# TechnoPoliceBadge.net
KiCad netlist of a schematic drawn in Altium Designer
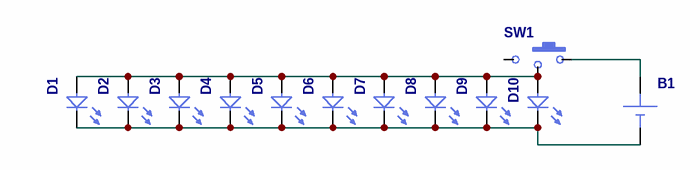
[diagram p0: TechnoPoliceBadge.SchDoc]

(export (version "E")
  (design (tool "Eeschema 10.0.6"))
  (components
    (comp (ref "B1")
      (value "BAT-HLD-001-TR")
      (footprint "BAT-HLD-001")
      (description "Coin Cell Battery Holders Linx CR2032 Battery Holder, Tape n Reel")
      (fields (field (name "MANUFACTURER") "Linx Technologies"))
      (libsource (lib "7Sigma") (part "BATT"))
    )
    (comp (ref "D1")
      (value "OL_RGB_IC_0807")
      (footprint "OL_0807")
      (description "RGB Diode with integrated driver. Fast Flashing")
      (fields (field (name "MANUFACTURER") "Aliexpress") (field (name "MANUFACTURER PART NUMBER") "None"))
      (libsource (lib "7Sigma") (part "OL_W"))
    )
    (comp (ref "D2")
      (value "OL_RGB_IC_0807")
      (footprint "OL_0807")
      (description "RGB Diode with integrated driver. Fast Flashing")
      (fields (field (name "MANUFACTURER") "Aliexpress") (field (name "MANUFACTURER PART NUMBER") "None"))
      (libsource (lib "7Sigma") (part "OL_W"))
    )
    (comp (ref "D3")
      (value "OL_RGB_IC_0807")
      (footprint "OL_0807")
      (description "RGB Diode with integrated driver. Fast Flashing")
      (fields (field (name "MANUFACTURER") "Aliexpress") (field (name "MANUFACTURER PART NUMBER") "None"))
      (libsource (lib "7Sigma") (part "OL_W"))
    )
    (comp (ref "D4")
      (value "OL_RGB_IC_0807")
      (footprint "OL_0807")
      (description "RGB Diode with integrated driver. Fast Flashing")
      (fields (field (name "MANUFACTURER") "Aliexpress") (field (name "MANUFACTURER PART NUMBER") "None"))
      (libsource (lib "7Sigma") (part "OL_W"))
    )
    (comp (ref "D5")
      (value "OL_RGB_IC_0807")
      (footprint "OL_0807")
      (description "RGB Diode with integrated driver. Fast Flashing")
      (fields (field (name "MANUFACTURER") "Aliexpress") (field (name "MANUFACTURER PART NUMBER") "None"))
      (libsource (lib "7Sigma") (part "OL_W"))
    )
    (comp (ref "D6")
      (value "OL_RGB_IC_0807")
      (footprint "OL_0807")
      (description "RGB Diode with integrated driver. Fast Flashing")
      (fields (field (name "MANUFACTURER") "Aliexpress") (field (name "MANUFACTURER PART NUMBER") "None"))
      (libsource (lib "7Sigma") (part "OL_W"))
    )
    (comp (ref "D7")
      (value "OL_RGB_IC_0807")
      (footprint "OL_0807")
      (description "RGB Diode with integrated driver. Fast Flashing")
      (fields (field (name "MANUFACTURER") "Aliexpress") (field (name "MANUFACTURER PART NUMBER") "None"))
      (libsource (lib "7Sigma") (part "OL_W"))
    )
    (comp (ref "D8")
      (value "OL_RGB_IC_0807")
      (footprint "OL_0807")
      (description "RGB Diode with integrated driver. Fast Flashing")
      (fields (field (name "MANUFACTURER") "Aliexpress") (field (name "MANUFACTURER PART NUMBER") "None"))
      (libsource (lib "7Sigma") (part "OL_W"))
    )
    (comp (ref "D9")
      (value "OL_RGB_IC_0807")
      (footprint "OL_0807")
      (description "RGB Diode with integrated driver. Fast Flashing")
      (fields (field (name "MANUFACTURER") "Aliexpress") (field (name "MANUFACTURER PART NUMBER") "None"))
      (libsource (lib "7Sigma") (part "OL_W"))
    )
    (comp (ref "D10")
      (value "OL_RGB_IC_0807")
      (footprint "OL_0807")
      (description "RGB Diode with integrated driver. Fast Flashing")
      (fields (field (name "MANUFACTURER") "Aliexpress") (field (name "MANUFACTURER PART NUMBER") "None"))
      (libsource (lib "7Sigma") (part "OL_W"))
    )
    (comp (ref "SW1")
      (value "MSK-12C01-07")
      (footprint "MSK-12C01-07")
      (description "SMT Slide Switch")
      (libsource (lib "7Sigma") (part "MSK-12C01-07"))
    )
  )
  (nets
    (net (code "1") (name "Net-(B1-PadPOS)") (class "Default")
      (node (ref "B1") (pin "POS") (pinfunction "POS_POS") (pintype "passive"))
      (node (ref "SW1") (pin "3") (pinfunction "3_3") (pintype "passive"))
    )
    (net (code "2") (name "Net-(D1-A)") (class "Default")
      (node (ref "D1") (pin "2") (pinfunction "A_2") (pintype "passive"))
      (node (ref "D10") (pin "2") (pinfunction "A_2") (pintype "passive"))
      (node (ref "D2") (pin "2") (pinfunction "A_2") (pintype "passive"))
      (node (ref "D3") (pin "2") (pinfunction "A_2") (pintype "passive"))
      (node (ref "D4") (pin "2") (pinfunction "A_2") (pintype "passive"))
      (node (ref "D5") (pin "2") (pinfunction "A_2") (pintype "passive"))
      (node (ref "D6") (pin "2") (pinfunction "A_2") (pintype "passive"))
      (node (ref "D7") (pin "2") (pinfunction "A_2") (pintype "passive"))
      (node (ref "D8") (pin "2") (pinfunction "A_2") (pintype "passive"))
      (node (ref "D9") (pin "2") (pinfunction "A_2") (pintype "passive"))
      (node (ref "SW1") (pin "2") (pinfunction "2_2") (pintype "passive"))
    )
    (net (code "3") (name "Net-(D1-C)") (class "Default")
      (node (ref "B1") (pin "NEG") (pinfunction "NEG_NEG") (pintype "passive"))
      (node (ref "D1") (pin "1") (pinfunction "C_1") (pintype "passive"))
      (node (ref "D10") (pin "1") (pinfunction "C_1") (pintype "passive"))
      (node (ref "D2") (pin "1") (pinfunction "C_1") (pintype "passive"))
      (node (ref "D3") (pin "1") (pinfunction "C_1") (pintype "passive"))
      (node (ref "D4") (pin "1") (pinfunction "C_1") (pintype "passive"))
      (node (ref "D5") (pin "1") (pinfunction "C_1") (pintype "passive"))
      (node (ref "D6") (pin "1") (pinfunction "C_1") (pintype "passive"))
      (node (ref "D7") (pin "1") (pinfunction "C_1") (pintype "passive"))
      (node (ref "D8") (pin "1") (pinfunction "C_1") (pintype "passive"))
      (node (ref "D9") (pin "1") (pinfunction "C_1") (pintype "passive"))
    )
    (net (code "4") (name "unconnected-(SW1-Pad1)") (class "Default")
      (node (ref "SW1") (pin "1") (pinfunction "1_1") (pintype "passive"))
    )
  )
)
